# Overview_and_Power.net
KiCad netlist of a schematic drawn in Altium Designer
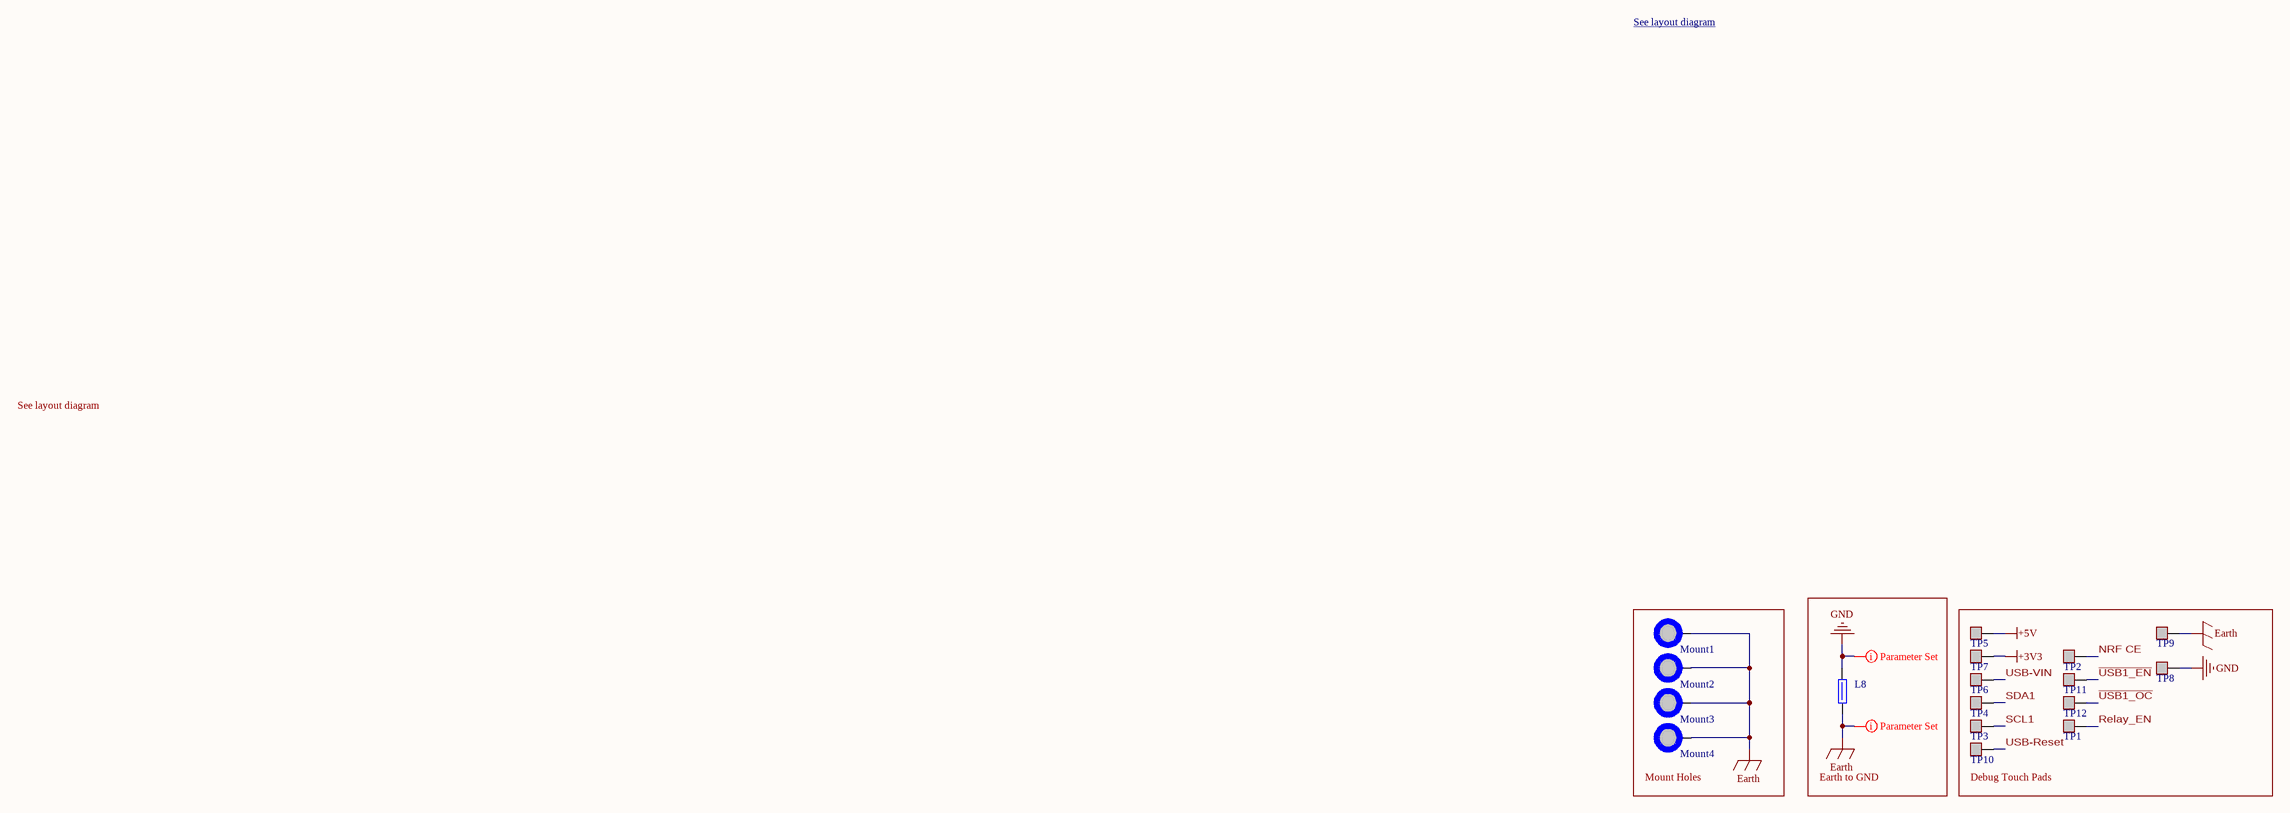
[diagram p0: Overview and Power.SchDoc]

(export (version "E")
  (design (tool "Eeschema 10.0.6"))
  (components
    (comp (ref "L8")
      (value "742792040")
      (footprint "[Ferrite] SMD Bead 0805 (2)")
      (libsource (lib "RADM Components") (part "[Ferrite] SMD Ferrite Bead (2)"))
    )
    (comp (ref "Mount1")
      (value "M3 Mount Hole")
      (footprint "[Mount] M3 Mount Hole")
      (description "Place at least 4.5mm from board edge. Plated.")
      (libsource (lib "RADM Connectors") (part "[Mount] M3 Mount Hole"))
    )
    (comp (ref "Mount2")
      (value "M3 Mount Hole")
      (footprint "[Mount] M3 Mount Hole")
      (description "Place at least 4.5mm from board edge. Plated.")
      (libsource (lib "RADM Connectors") (part "[Mount] M3 Mount Hole"))
    )
    (comp (ref "Mount3")
      (value "M3 Mount Hole")
      (footprint "[Mount] M3 Mount Hole")
      (description "Place at least 4.5mm from board edge. Plated.")
      (libsource (lib "RADM Connectors") (part "[Mount] M3 Mount Hole"))
    )
    (comp (ref "Mount4")
      (value "M3 Mount Hole")
      (footprint "[Mount] M3 Mount Hole")
      (description "Place at least 4.5mm from board edge. Plated.")
      (libsource (lib "RADM Connectors") (part "[Mount] M3 Mount Hole"))
    )
    (comp (ref "TP1")
      (value "Probe Pad")
      (footprint "[Probe] Touch Pad")
      (libsource (lib "RADM Connectors") (part "[Probe] Touch Pad"))
    )
    (comp (ref "TP2")
      (value "Probe Pad")
      (footprint "[Probe] Touch Pad")
      (libsource (lib "RADM Connectors") (part "[Probe] Touch Pad"))
    )
    (comp (ref "TP3")
      (value "Probe Pad")
      (footprint "[Probe] Touch Pad")
      (libsource (lib "RADM Connectors") (part "[Probe] Touch Pad"))
    )
    (comp (ref "TP4")
      (value "Probe Pad")
      (footprint "[Probe] Touch Pad")
      (libsource (lib "RADM Connectors") (part "[Probe] Touch Pad"))
    )
    (comp (ref "TP5")
      (value "Probe Pad")
      (footprint "[Probe] Touch Pad")
      (libsource (lib "RADM Connectors") (part "[Probe] Touch Pad"))
    )
    (comp (ref "TP6")
      (value "Probe Pad")
      (footprint "[Probe] Touch Pad")
      (libsource (lib "RADM Connectors") (part "[Probe] Touch Pad"))
    )
    (comp (ref "TP7")
      (value "Probe Pad")
      (footprint "[Probe] Touch Pad")
      (libsource (lib "RADM Connectors") (part "[Probe] Touch Pad"))
    )
    (comp (ref "TP8")
      (value "Probe Pad")
      (footprint "[Probe] Touch Pad")
      (libsource (lib "RADM Connectors") (part "[Probe] Touch Pad"))
    )
    (comp (ref "TP9")
      (value "Probe Pad")
      (footprint "[Probe] Touch Pad")
      (libsource (lib "RADM Connectors") (part "[Probe] Touch Pad"))
    )
    (comp (ref "TP10")
      (value "Probe Pad")
      (footprint "[Probe] Touch Pad")
      (libsource (lib "RADM Connectors") (part "[Probe] Touch Pad"))
    )
    (comp (ref "TP11")
      (value "Probe Pad")
      (footprint "[Probe] Touch Pad")
      (libsource (lib "RADM Connectors") (part "[Probe] Touch Pad"))
    )
    (comp (ref "TP12")
      (value "Probe Pad")
      (footprint "[Probe] Touch Pad")
      (libsource (lib "RADM Connectors") (part "[Probe] Touch Pad"))
    )
  )
  (nets
    (net (code "1") (name "+3V3") (class "Default")
      (node (ref "TP7") (pin "1") (pinfunction "1_1") (pintype "passive"))
    )
    (net (code "2") (name "+5V") (class "Default")
      (node (ref "TP5") (pin "1") (pinfunction "1_1") (pintype "passive"))
    )
    (net (code "3") (name "/NRF CE") (class "Default")
      (node (ref "TP2") (pin "1") (pinfunction "1_1") (pintype "passive"))
    )
    (net (code "4") (name "/Relay_EN") (class "Default")
      (node (ref "TP1") (pin "1") (pinfunction "1_1") (pintype "passive"))
    )
    (net (code "5") (name "/SCL1") (class "Default")
      (node (ref "TP3") (pin "1") (pinfunction "1_1") (pintype "passive"))
    )
    (net (code "6") (name "/SDA1") (class "Default")
      (node (ref "TP4") (pin "1") (pinfunction "1_1") (pintype "passive"))
    )
    (net (code "7") (name "/USB-Reset") (class "Default")
      (node (ref "TP10") (pin "1") (pinfunction "1_1") (pintype "passive"))
    )
    (net (code "8") (name "/USB-VIN") (class "Default")
      (node (ref "TP6") (pin "1") (pinfunction "1_1") (pintype "passive"))
    )
    (net (code "9") (name "/USB1_EN") (class "Default")
      (node (ref "TP11") (pin "1") (pinfunction "1_1") (pintype "passive"))
    )
    (net (code "10") (name "/USB1_OC") (class "Default")
      (node (ref "TP12") (pin "1") (pinfunction "1_1") (pintype "passive"))
    )
    (net (code "11") (name "Earth") (class "Default")
      (node (ref "L8") (pin "1") (pinfunction "1_1") (pintype "passive"))
      (node (ref "Mount1") (pin "1") (pintype "power_in"))
      (node (ref "Mount2") (pin "1") (pintype "power_in"))
      (node (ref "Mount3") (pin "1") (pintype "power_in"))
      (node (ref "Mount4") (pin "1") (pintype "power_in"))
      (node (ref "TP9") (pin "1") (pinfunction "1_1") (pintype "passive"))
    )
    (net (code "12") (name "GND") (class "Default")
      (node (ref "L8") (pin "2") (pinfunction "2_2") (pintype "passive"))
      (node (ref "TP8") (pin "1") (pinfunction "1_1") (pintype "passive"))
    )
  )
)
